# FPGA_Power_SPI.net
KiCad netlist of a schematic drawn in Altium Designer
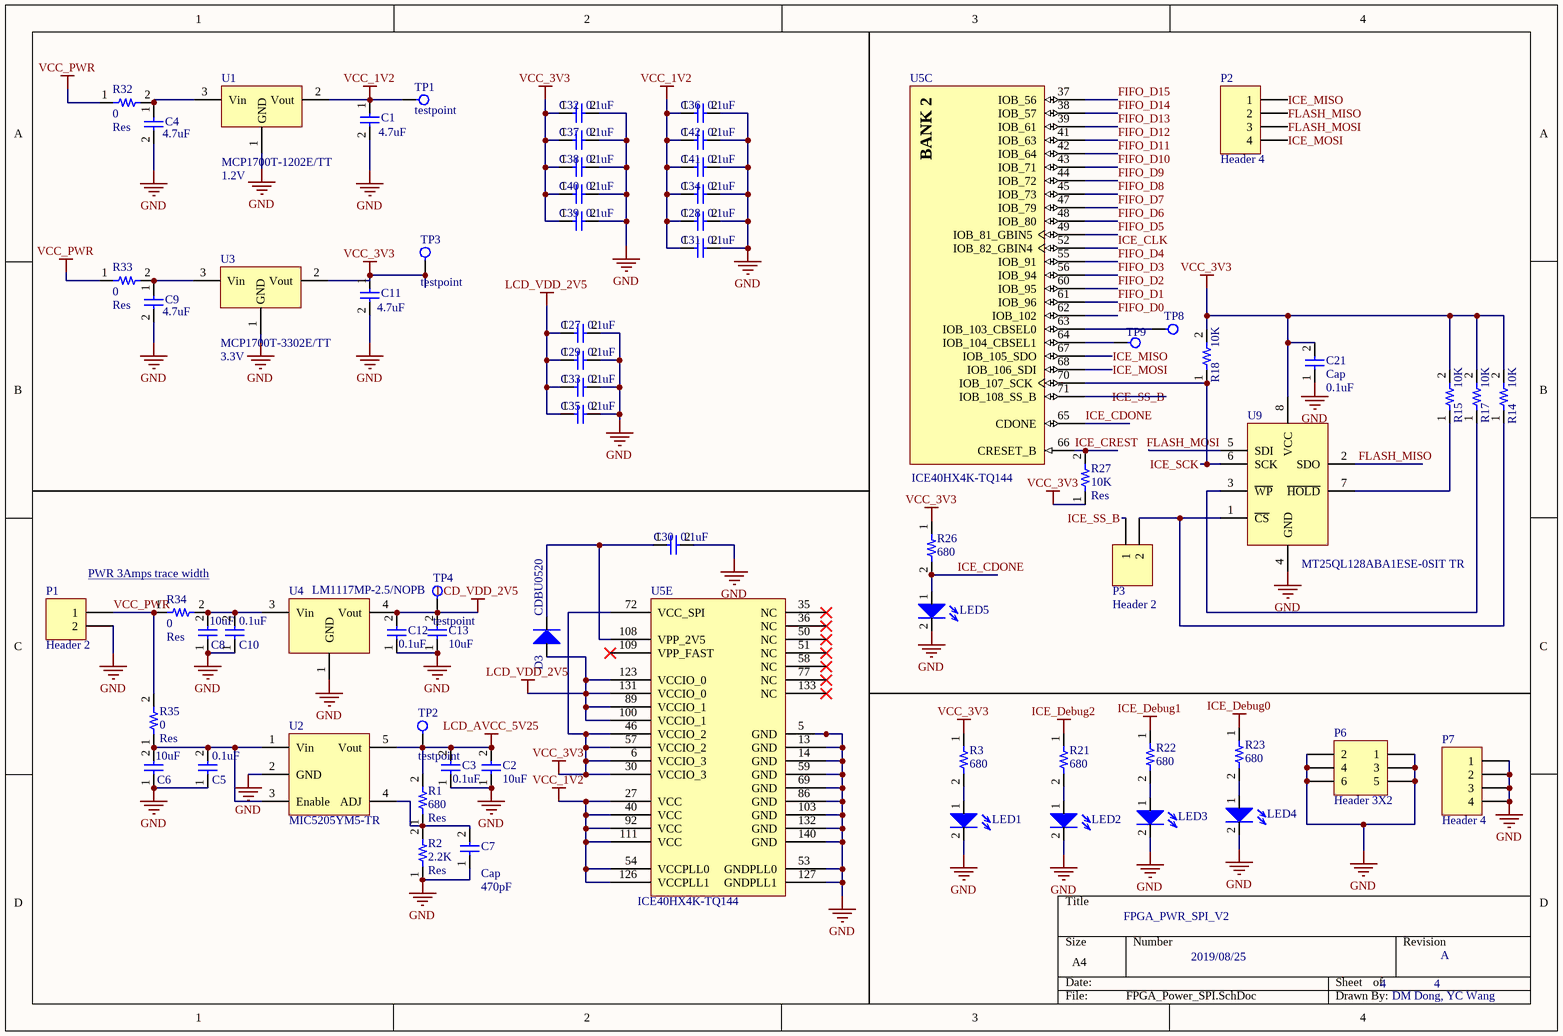
[diagram p0: FPGA_Power_SPI.SchDoc]

(export (version "E")
  (design (tool "Eeschema 10.0.6"))
  (components
    (comp (ref "C1")
      (value "4.7uF")
      (footprint "Cap_4.7uF")
      (description "Multilayer Ceramic Capacitors MLCC - SMD/SMT 6.3V 4.7uF 0603 X5R 10%")
      (fields (field (name "Comment") "C0603C475K9PAC7411") (field (name "CREATED BY") "Daoming Dong"))
      (libsource (lib "USB_FPGA_SLM_v1") (part "Cap_4.7uF"))
    )
    (comp (ref "C2")
      (value "10uF")
      (footprint "Cap_10uF")
      (description "Multilayer Ceramic Capacitors MLCC - SMD/SMT 0603 6.3V 10uF X5R 10% Soft Term")
      (fields (field (name "Comment") "C1608X5R0J106K080AE") (field (name "CREATED BY") "Daoming Dong"))
      (libsource (lib "USB_FPGA_SLM_v1") (part "Cap_10uF"))
    )
    (comp (ref "C3")
      (value "0.1uF")
      (footprint "Cap_0.1uF")
      (description "Multilayer Ceramic Capacitors MLCC - SMD/SMT 0.1uF 10% 50V AEC-Q200")
      (fields (field (name "Comment") "AC0603KRX7R9BB104") (field (name "CREATED BY") "Daoming Dong"))
      (libsource (lib "USB_FPGA_SLM_v1") (part "Cap_0.1uF"))
    )
    (comp (ref "C4")
      (value "4.7uF")
      (footprint "Cap_4.7uF")
      (description "Multilayer Ceramic Capacitors MLCC - SMD/SMT 6.3V 4.7uF 0603 X5R 10%")
      (fields (field (name "Comment") "C0603C475K9PAC7411") (field (name "CREATED BY") "Daoming Dong"))
      (libsource (lib "USB_FPGA_SLM_v1") (part "Cap_4.7uF"))
    )
    (comp (ref "C5")
      (value "0.1uF")
      (footprint "Cap_0.1uF")
      (description "Multilayer Ceramic Capacitors MLCC - SMD/SMT 0.1uF 10% 50V AEC-Q200")
      (fields (field (name "Comment") "AC0603KRX7R9BB104") (field (name "CREATED BY") "Daoming Dong"))
      (libsource (lib "USB_FPGA_SLM_v1") (part "Cap_0.1uF"))
    )
    (comp (ref "C6")
      (value "10uF")
      (footprint "Cap_10uF")
      (description "Multilayer Ceramic Capacitors MLCC - SMD/SMT 0603 6.3V 10uF X5R 10% Soft Term")
      (fields (field (name "Comment") "C1608X5R0J106K080AE") (field (name "CREATED BY") "Daoming Dong"))
      (libsource (lib "USB_FPGA_SLM_v1") (part "Cap_10uF"))
    )
    (comp (ref "C7")
      (value "470pF")
      (footprint "CAP_470pF")
      (description "Multilayer Ceramic Capacitors MLCC - SMD/SMT 25V 470pF X7R 0402 10% AEC-Q200")
      (fields
        (field (name "COMPONENT NAME") "Cap")
        (field (name "Comment") "C0402S471K3RACAUTO")
        (field (name "CREATED BY") "Daoming Dong")
      )
      (libsource (lib "USB_FPGA_SLM_v1") (part "Cap_470pF"))
    )
    (comp (ref "C8")
      (value "10uF")
      (footprint "Cap_10uF")
      (description "Multilayer Ceramic Capacitors MLCC - SMD/SMT 0603 6.3V 10uF X5R 10% Soft Term")
      (fields (field (name "Comment") "C1608X5R0J106K080AE") (field (name "CREATED BY") "Daoming Dong"))
      (libsource (lib "USB_FPGA_SLM_v1") (part "Cap_10uF"))
    )
    (comp (ref "C9")
      (value "4.7uF")
      (footprint "Cap_4.7uF")
      (description "Multilayer Ceramic Capacitors MLCC - SMD/SMT 6.3V 4.7uF 0603 X5R 10%")
      (fields (field (name "Comment") "C0603C475K9PAC7411") (field (name "CREATED BY") "Daoming Dong"))
      (libsource (lib "USB_FPGA_SLM_v1") (part "Cap_4.7uF"))
    )
    (comp (ref "C10")
      (value "0.1uF")
      (footprint "Cap_0.1uF")
      (description "Multilayer Ceramic Capacitors MLCC - SMD/SMT 0.1uF 10% 50V AEC-Q200")
      (fields (field (name "Comment") "AC0603KRX7R9BB104") (field (name "CREATED BY") "Daoming Dong"))
      (libsource (lib "USB_FPGA_SLM_v1") (part "Cap_0.1uF"))
    )
    (comp (ref "C11")
      (value "4.7uF")
      (footprint "Cap_4.7uF")
      (description "Multilayer Ceramic Capacitors MLCC - SMD/SMT 6.3V 4.7uF 0603 X5R 10%")
      (fields (field (name "Comment") "C0603C475K9PAC7411") (field (name "CREATED BY") "Daoming Dong"))
      (libsource (lib "USB_FPGA_SLM_v1") (part "Cap_4.7uF"))
    )
    (comp (ref "C12")
      (value "0.1uF")
      (footprint "Cap_0.1uF")
      (description "Multilayer Ceramic Capacitors MLCC - SMD/SMT 0.1uF 10% 50V AEC-Q200")
      (fields (field (name "Comment") "AC0603KRX7R9BB104") (field (name "CREATED BY") "Daoming Dong"))
      (libsource (lib "USB_FPGA_SLM_v1") (part "Cap_0.1uF"))
    )
    (comp (ref "C13")
      (value "10uF")
      (footprint "Cap_10uF")
      (description "Multilayer Ceramic Capacitors MLCC - SMD/SMT 0603 6.3V 10uF X5R 10% Soft Term")
      (fields (field (name "Comment") "C1608X5R0J106K080AE") (field (name "CREATED BY") "Daoming Dong"))
      (libsource (lib "USB_FPGA_SLM_v1") (part "Cap_10uF"))
    )
    (comp (ref "C21")
      (value "0.1uF")
      (footprint "Cap_0.1uF")
      (description "Multilayer Ceramic Capacitors MLCC - SMD/SMT 0.1uF 10% 50V AEC-Q200")
      (fields
        (field (name "COMPONENT NAME") "Cap")
        (field (name "Comment") "AC0603KRX7R9BB104")
        (field (name "CREATED BY") "Daoming Dong")
      )
      (libsource (lib "USB_FPGA_SLM_v1") (part "Cap_0.1uF"))
    )
    (comp (ref "C27")
      (value "0.1uF")
      (footprint "Cap_0.1uF")
      (description "Multilayer Ceramic Capacitors MLCC - SMD/SMT 0.1uF 10% 50V AEC-Q200")
      (fields (field (name "Comment") "AC0603KRX7R9BB104") (field (name "CREATED BY") "Daoming Dong"))
      (libsource (lib "USB_FPGA_SLM_v1") (part "Cap_0.1uF"))
    )
    (comp (ref "C28")
      (value "0.1uF")
      (footprint "Cap_0.1uF")
      (description "Multilayer Ceramic Capacitors MLCC - SMD/SMT 0.1uF 10% 50V AEC-Q200")
      (fields (field (name "Comment") "AC0603KRX7R9BB104") (field (name "CREATED BY") "Daoming Dong"))
      (libsource (lib "USB_FPGA_SLM_v1") (part "Cap_0.1uF"))
    )
    (comp (ref "C29")
      (value "0.1uF")
      (footprint "Cap_0.1uF")
      (description "Multilayer Ceramic Capacitors MLCC - SMD/SMT 0.1uF 10% 50V AEC-Q200")
      (fields (field (name "Comment") "AC0603KRX7R9BB104") (field (name "CREATED BY") "Daoming Dong"))
      (libsource (lib "USB_FPGA_SLM_v1") (part "Cap_0.1uF"))
    )
    (comp (ref "C30")
      (value "0.1uF")
      (footprint "Cap_0.1uF")
      (description "Multilayer Ceramic Capacitors MLCC - SMD/SMT 0.1uF 10% 50V AEC-Q200")
      (fields (field (name "Comment") "AC0603KRX7R9BB104") (field (name "CREATED BY") "Daoming Dong"))
      (libsource (lib "USB_FPGA_SLM_v1") (part "Cap_0.1uF"))
    )
    (comp (ref "C31")
      (value "0.1uF")
      (footprint "Cap_0.1uF")
      (description "Multilayer Ceramic Capacitors MLCC - SMD/SMT 0.1uF 10% 50V AEC-Q200")
      (fields (field (name "Comment") "AC0603KRX7R9BB104") (field (name "CREATED BY") "Daoming Dong"))
      (libsource (lib "USB_FPGA_SLM_v1") (part "Cap_0.1uF"))
    )
    (comp (ref "C32")
      (value "0.1uF")
      (footprint "Cap_0.1uF")
      (description "Multilayer Ceramic Capacitors MLCC - SMD/SMT 0.1uF 10% 50V AEC-Q200")
      (fields (field (name "Comment") "AC0603KRX7R9BB104") (field (name "CREATED BY") "Daoming Dong"))
      (libsource (lib "USB_FPGA_SLM_v1") (part "Cap_0.1uF"))
    )
    (comp (ref "C33")
      (value "0.1uF")
      (footprint "Cap_0.1uF")
      (description "Multilayer Ceramic Capacitors MLCC - SMD/SMT 0.1uF 10% 50V AEC-Q200")
      (fields (field (name "Comment") "AC0603KRX7R9BB104") (field (name "CREATED BY") "Daoming Dong"))
      (libsource (lib "USB_FPGA_SLM_v1") (part "Cap_0.1uF"))
    )
    (comp (ref "C34")
      (value "0.1uF")
      (footprint "Cap_0.1uF")
      (description "Multilayer Ceramic Capacitors MLCC - SMD/SMT 0.1uF 10% 50V AEC-Q200")
      (fields (field (name "Comment") "AC0603KRX7R9BB104") (field (name "CREATED BY") "Daoming Dong"))
      (libsource (lib "USB_FPGA_SLM_v1") (part "Cap_0.1uF"))
    )
    (comp (ref "C35")
      (value "0.1uF")
      (footprint "Cap_0.1uF")
      (description "Multilayer Ceramic Capacitors MLCC - SMD/SMT 0.1uF 10% 50V AEC-Q200")
      (fields (field (name "Comment") "AC0603KRX7R9BB104") (field (name "CREATED BY") "Daoming Dong"))
      (libsource (lib "USB_FPGA_SLM_v1") (part "Cap_0.1uF"))
    )
    (comp (ref "C36")
      (value "0.1uF")
      (footprint "Cap_0.1uF")
      (description "Multilayer Ceramic Capacitors MLCC - SMD/SMT 0.1uF 10% 50V AEC-Q200")
      (fields (field (name "Comment") "AC0603KRX7R9BB104") (field (name "CREATED BY") "Daoming Dong"))
      (libsource (lib "USB_FPGA_SLM_v1") (part "Cap_0.1uF"))
    )
    (comp (ref "C37")
      (value "0.1uF")
      (footprint "Cap_0.1uF")
      (description "Multilayer Ceramic Capacitors MLCC - SMD/SMT 0.1uF 10% 50V AEC-Q200")
      (fields (field (name "Comment") "AC0603KRX7R9BB104") (field (name "CREATED BY") "Daoming Dong"))
      (libsource (lib "USB_FPGA_SLM_v1") (part "Cap_0.1uF"))
    )
    (comp (ref "C38")
      (value "0.1uF")
      (footprint "Cap_0.1uF")
      (description "Multilayer Ceramic Capacitors MLCC - SMD/SMT 0.1uF 10% 50V AEC-Q200")
      (fields (field (name "Comment") "AC0603KRX7R9BB104") (field (name "CREATED BY") "Daoming Dong"))
      (libsource (lib "USB_FPGA_SLM_v1") (part "Cap_0.1uF"))
    )
    (comp (ref "C39")
      (value "0.1uF")
      (footprint "Cap_0.1uF")
      (description "Multilayer Ceramic Capacitors MLCC - SMD/SMT 0.1uF 10% 50V AEC-Q200")
      (fields (field (name "Comment") "AC0603KRX7R9BB104") (field (name "CREATED BY") "Daoming Dong"))
      (libsource (lib "USB_FPGA_SLM_v1") (part "Cap_0.1uF"))
    )
    (comp (ref "C40")
      (value "0.1uF")
      (footprint "Cap_0.1uF")
      (description "Multilayer Ceramic Capacitors MLCC - SMD/SMT 0.1uF 10% 50V AEC-Q200")
      (fields (field (name "Comment") "AC0603KRX7R9BB104") (field (name "CREATED BY") "Daoming Dong"))
      (libsource (lib "USB_FPGA_SLM_v1") (part "Cap_0.1uF"))
    )
    (comp (ref "C41")
      (value "0.1uF")
      (footprint "Cap_0.1uF")
      (description "Multilayer Ceramic Capacitors MLCC - SMD/SMT 0.1uF 10% 50V AEC-Q200")
      (fields (field (name "Comment") "AC0603KRX7R9BB104") (field (name "CREATED BY") "Daoming Dong"))
      (libsource (lib "USB_FPGA_SLM_v1") (part "Cap_0.1uF"))
    )
    (comp (ref "C42")
      (value "0.1uF")
      (footprint "Cap_0.1uF")
      (description "Multilayer Ceramic Capacitors MLCC - SMD/SMT 0.1uF 10% 50V AEC-Q200")
      (fields (field (name "Comment") "AC0603KRX7R9BB104") (field (name "CREATED BY") "Daoming Dong"))
      (libsource (lib "USB_FPGA_SLM_v1") (part "Cap_0.1uF"))
    )
    (comp (ref "D3")
      (value "CDBU0520")
      (footprint "SchottkyDiode_CDBU0520")
      (description "Schottky Diodes & Rectifiers VR=20V, IO=500mA")
      (fields (field (name "CREATED BY") "Daoming Dong"))
      (libsource (lib "USB_FPGA_SLM_v1") (part "SDiode_CDBU0520"))
    )
    (comp (ref "LED1")
      (value "TLMS1000-GS08")
      (footprint "LED_RED")
      (description "Standard LEDs - SMD RED")
      (fields (field (name "CREATED BY") "Daoming Dong"))
      (libsource (lib "USB_FPGA_SLM_v1") (part "LED_RED"))
    )
    (comp (ref "LED2")
      (value "TLMS1000-GS08")
      (footprint "LED_RED")
      (description "Standard LEDs - SMD RED")
      (fields (field (name "CREATED BY") "Daoming Dong"))
      (libsource (lib "USB_FPGA_SLM_v1") (part "LED_RED"))
    )
    (comp (ref "LED3")
      (value "TLMS1000-GS08")
      (footprint "LED_RED")
      (description "Standard LEDs - SMD RED")
      (fields (field (name "CREATED BY") "Daoming Dong"))
      (libsource (lib "USB_FPGA_SLM_v1") (part "LED_RED"))
    )
    (comp (ref "LED4")
      (value "TLMS1000-GS08")
      (footprint "LED_RED")
      (description "Standard LEDs - SMD RED")
      (fields (field (name "CREATED BY") "Daoming Dong"))
      (libsource (lib "USB_FPGA_SLM_v1") (part "LED_RED"))
    )
    (comp (ref "LED5")
      (value "TLMS1000-GS08")
      (footprint "LED_RED")
      (description "Standard LEDs - SMD RED")
      (fields (field (name "CREATED BY") "Daoming Dong"))
      (libsource (lib "USB_FPGA_SLM_v1") (part "LED_RED"))
    )
    (comp (ref "P1")
      (value "Header 2")
      (footprint "HDR1X2")
      (description "Header, 2-Pin")
      (fields (field (name "PUBLISHER") "Altium Limited"))
      (libsource (lib "") (part "Header 2_1"))
    )
    (comp (ref "P2")
      (value "Header 4")
      (footprint "HDR2X2")
      (description "Header, 4-Pin")
      (fields (field (name "PUBLISHER") "Altium Limited"))
      (libsource (lib "Miscellaneous Connectors") (part "Header 4"))
    )
    (comp (ref "P3")
      (value "Header 2")
      (footprint "HDR1X2")
      (description "Header, 2-Pin")
      (fields (field (name "PUBLISHER") "Altium Limited"))
      (libsource (lib "Miscellaneous Connectors") (part "Header 2"))
    )
    (comp (ref "P6")
      (value "Header 3X2")
      (footprint "HDR2X3")
      (description "Header, 3-Pin, Dual row")
      (fields (field (name "PUBLISHER") "Altium Limited"))
      (libsource (lib "Miscellaneous Connectors") (part "Header 3X2"))
    )
    (comp (ref "P7")
      (value "Header 4")
      (footprint "HDR2X2")
      (description "Header, 4-Pin")
      (fields (field (name "PUBLISHER") "Altium Limited"))
      (libsource (lib "Miscellaneous Connectors") (part "Header 4"))
    )
    (comp (ref "R1")
      (value "680")
      (footprint "RES_680")
      (description "Thin Film Resistors - SMD 680 ohm 1% 50 ppm Thin Film")
      (fields
        (field (name "COMPONENT NAME") "Res")
        (field (name "Comment") "RT0603FRE13680RL")
        (field (name "CREATED BY") "Daoming Dong")
      )
      (libsource (lib "USB_FPGA_SLM_v1") (part "Res_680"))
    )
    (comp (ref "R2")
      (value "2.2K")
      (footprint "RES_2.2K")
      (description "Thick Film Resistors - SMD 1/10Watt 2.2Kohms 5% Commercial Use")
      (fields
        (field (name "COMPONENT NAME") "Res")
        (field (name "Comment") "CRCW06032K20JNEAC")
        (field (name "CREATED BY") "Daoming Dong")
      )
      (libsource (lib "USB_FPGA_SLM_v1") (part "Res_2.2K"))
    )
    (comp (ref "R3")
      (value "680")
      (footprint "RES_680")
      (description "Thin Film Resistors - SMD 680 ohm 1% 50 ppm Thin Film")
      (fields (field (name "Comment") "RT0603FRE13680RL") (field (name "CREATED BY") "Daoming Dong"))
      (libsource (lib "USB_FPGA_SLM_v1") (part "Res_680"))
    )
    (comp (ref "R14")
      (value "10K")
      (footprint "RES_10K")
      (description "Thin Film Resistors - SMD 10K ohm 0.05% 50 ppm High-Precision")
      (fields (field (name "Comment") "RT0603WRE0710KL") (field (name "CREATED BY") "Daoming Dong"))
      (libsource (lib "USB_FPGA_SLM_v1") (part "Res_10K"))
    )
    (comp (ref "R15")
      (value "10K")
      (footprint "RES_10K")
      (description "Thin Film Resistors - SMD 10K ohm 0.05% 50 ppm High-Precision")
      (fields (field (name "Comment") "RT0603WRE0710KL") (field (name "CREATED BY") "Daoming Dong"))
      (libsource (lib "USB_FPGA_SLM_v1") (part "Res_10K"))
    )
    (comp (ref "R17")
      (value "10K")
      (footprint "RES_10K")
      (description "Thin Film Resistors - SMD 10K ohm 0.05% 50 ppm High-Precision")
      (fields (field (name "Comment") "RT0603WRE0710KL") (field (name "CREATED BY") "Daoming Dong"))
      (libsource (lib "USB_FPGA_SLM_v1") (part "Res_10K"))
    )
    (comp (ref "R18")
      (value "10K")
      (footprint "RES_10K")
      (description "Thin Film Resistors - SMD 10K ohm 0.05% 50 ppm High-Precision")
      (fields (field (name "Comment") "RT0603WRE0710KL") (field (name "CREATED BY") "Daoming Dong"))
      (libsource (lib "USB_FPGA_SLM_v1") (part "Res_10K"))
    )
    (comp (ref "R21")
      (value "680")
      (footprint "RES_680")
      (description "Thin Film Resistors - SMD 680 ohm 1% 50 ppm Thin Film")
      (fields (field (name "Comment") "RT0603FRE13680RL") (field (name "CREATED BY") "Daoming Dong"))
      (libsource (lib "USB_FPGA_SLM_v1") (part "Res_680"))
    )
    (comp (ref "R22")
      (value "680")
      (footprint "RES_680")
      (description "Thin Film Resistors - SMD 680 ohm 1% 50 ppm Thin Film")
      (fields (field (name "Comment") "RT0603FRE13680RL") (field (name "CREATED BY") "Daoming Dong"))
      (libsource (lib "USB_FPGA_SLM_v1") (part "Res_680"))
    )
    (comp (ref "R23")
      (value "680")
      (footprint "RES_680")
      (description "Thin Film Resistors - SMD 680 ohm 1% 50 ppm Thin Film")
      (fields (field (name "Comment") "RT0603FRE13680RL") (field (name "CREATED BY") "Daoming Dong"))
      (libsource (lib "USB_FPGA_SLM_v1") (part "Res_680"))
    )
    (comp (ref "R26")
      (value "680")
      (footprint "RES_680")
      (description "Thin Film Resistors - SMD 680 ohm 1% 50 ppm Thin Film")
      (fields (field (name "Comment") "RT0603FRE13680RL") (field (name "CREATED BY") "Daoming Dong"))
      (libsource (lib "USB_FPGA_SLM_v1") (part "Res_680"))
    )
    (comp (ref "R27")
      (value "10K")
      (footprint "RES_10K")
      (description "Thin Film Resistors - SMD 10K ohm 0.05% 50 ppm High-Precision")
      (fields
        (field (name "COMPONENT NAME") "Res")
        (field (name "Comment") "RT0603WRE0710KL")
        (field (name "CREATED BY") "Daoming Dong")
      )
      (libsource (lib "USB_FPGA_SLM_v1") (part "Res_10K"))
    )
    (comp (ref "R32")
      (value "0")
      (footprint "RES_0")
      (description "Thick Film Resistors - SMD 1/10Watt 0ohms Commercial Use")
      (fields
        (field (name "COMPONENT NAME") "Res")
        (field (name "Comment") "CRCW06030000Z0EAC")
        (field (name "CREATED BY") "Daoming Dong")
      )
      (libsource (lib "USB_FPGA_SLM_v1") (part "Res_0"))
    )
    (comp (ref "R33")
      (value "0")
      (footprint "RES_0")
      (description "Thick Film Resistors - SMD 1/10Watt 0ohms Commercial Use")
      (fields
        (field (name "COMPONENT NAME") "Res")
        (field (name "Comment") "CRCW06030000Z0EAC")
        (field (name "CREATED BY") "Daoming Dong")
      )
      (libsource (lib "USB_FPGA_SLM_v1") (part "Res_0"))
    )
    (comp (ref "R34")
      (value "0")
      (footprint "RES_0")
      (description "Thick Film Resistors - SMD 1/10Watt 0ohms Commercial Use")
      (fields
        (field (name "COMPONENT NAME") "Res")
        (field (name "Comment") "CRCW06030000Z0EAC")
        (field (name "CREATED BY") "Daoming Dong")
      )
      (libsource (lib "USB_FPGA_SLM_v1") (part "Res_0"))
    )
    (comp (ref "R35")
      (value "0")
      (footprint "RES_0")
      (description "Thick Film Resistors - SMD 1/10Watt 0ohms Commercial Use")
      (fields
        (field (name "COMPONENT NAME") "Res")
        (field (name "Comment") "CRCW06030000Z0EAC")
        (field (name "CREATED BY") "Daoming Dong")
      )
      (libsource (lib "USB_FPGA_SLM_v1") (part "Res_0"))
    )
    (comp (ref "TP1")
      (value "testpoint")
      (footprint "testpoint")
      (description "Testpoint for testing voltage")
      (fields (field (name "CREATED BY") "Daoming Dong"))
      (libsource (lib "USB_FPGA_SLM_v1") (part "Testpoint"))
    )
    (comp (ref "TP2")
      (value "testpoint")
      (footprint "testpoint")
      (description "Testpoint for testing voltage")
      (fields (field (name "CREATED BY") "Daoming Dong"))
      (libsource (lib "USB_FPGA_SLM_v1") (part "Testpoint"))
    )
    (comp (ref "TP3")
      (value "testpoint")
      (footprint "testpoint")
      (description "Testpoint for testing voltage")
      (fields (field (name "CREATED BY") "Daoming Dong"))
      (libsource (lib "USB_FPGA_SLM_v1") (part "Testpoint"))
    )
    (comp (ref "TP4")
      (value "testpoint")
      (footprint "testpoint")
      (description "Testpoint for testing voltage")
      (fields (field (name "CREATED BY") "Daoming Dong"))
      (libsource (lib "USB_FPGA_SLM_v1") (part "Testpoint"))
    )
    (comp (ref "TP8")
      (value "Testpoint")
      (footprint "testpoint")
      (description "Testpoint for testing voltage")
      (fields (field (name "CREATED BY") "Daoming Dong"))
      (libsource (lib "USB_FPGA_SLM_v1") (part "Testpoint"))
    )
    (comp (ref "TP9")
      (value "Testpoint")
      (footprint "testpoint")
      (description "Testpoint for testing voltage")
      (fields (field (name "CREATED BY") "Daoming Dong"))
      (libsource (lib "USB_FPGA_SLM_v1") (part "Testpoint"))
    )
    (comp (ref "U1")
      (value "MCP1700T-1202E/TT")
      (footprint "MIC_LDO_1V2")
      (description "LDO Voltage Regulators 250mA Adj LDO 2%")
      (fields (field (name "ALTIUM_VALUE") "1.2V") (field (name "CREATED BY") "Daoming Dong"))
      (libsource (lib "USB_FPGA_SLM_v1") (part "MIC_LDO_1V2"))
    )
    (comp (ref "U2")
      (value "MIC5205YM5-TR")
      (footprint "MIC5205YM5")
      (description "LDO Voltage Regulators 150mA 1% Low Noise LDO")
      (fields (field (name "CREATED BY") "Daoming Dong"))
      (libsource (lib "USB_FPGA_SLM_v1") (part "MIC5205YM5"))
    )
    (comp (ref "U3")
      (value "MCP1700T-3302E/TT")
      (footprint "MIC_LDO_3V3")
      (description "3.3v LDO Voltage Regulators 250mA Adj LDO 2%")
      (fields (field (name "ALTIUM_VALUE") "3.3V") (field (name "CREATED BY") "Daoming Dong"))
      (libsource (lib "USB_FPGA_SLM_v1") (part "MIC_LDO_3V3"))
    )
    (comp (ref "U4")
      (value "LM1117MP-2.5/NOPB")
      (footprint "LM1117MP-2.5/NOPB")
      (description "LDO Voltage Regulators 800mA LDO Linear Reg")
      (fields (field (name "CREATED BY") "Daoming Dong"))
      (libsource (lib "USB_FPGA_SLM_v1") (part "LDO_2V5"))
    )
    (comp (ref "U5")
      (value "ICE40HX4K-TQ144")
      (footprint "LATC-TQFP-144_L")
      (fields (field (name "MANUFACTURER") "Lattice Semiconductor"))
      (libsource (lib "Lattice iCE40") (part "ICE40HX4K-TQ144"))
    )
    (comp (ref "U9")
      (value "MT25QL128ABA1ESE-0SIT TR")
      (footprint "Flash")
      (description "NOR Flash SPI FLASH NOR SLC 32MX4 SOIC")
      (fields (field (name "CREATED BY") "Daoming Dong"))
      (libsource (lib "USB_FPGA_SLM_v1") (part "Flash"))
    )
  )
  (nets
    (net (code "1") (name "/FIFO_D0") (class "Default")
      (node (ref "U5") (pin "62") (pinfunction "IOB_102_62") (pintype "bidirectional"))
    )
    (net (code "2") (name "/FIFO_D1") (class "Default")
      (node (ref "U5") (pin "61") (pinfunction "IOB_96_61") (pintype "bidirectional"))
    )
    (net (code "3") (name "/FIFO_D2") (class "Default")
      (node (ref "U5") (pin "60") (pinfunction "IOB_95_60") (pintype "bidirectional"))
    )
    (net (code "4") (name "/FIFO_D3") (class "Default")
      (node (ref "U5") (pin "56") (pinfunction "IOB_94_56") (pintype "bidirectional"))
    )
    (net (code "5") (name "/FIFO_D4") (class "Default")
      (node (ref "U5") (pin "55") (pinfunction "IOB_91_55") (pintype "bidirectional"))
    )
    (net (code "6") (name "/FIFO_D5") (class "Default")
      (node (ref "U5") (pin "49") (pinfunction "IOB_81_GBIN5_49") (pintype "bidirectional"))
    )
    (net (code "7") (name "/FIFO_D6") (class "Default")
      (node (ref "U5") (pin "48") (pinfunction "IOB_80_48") (pintype "bidirectional"))
    )
    (net (code "8") (name "/FIFO_D7") (class "Default")
      (node (ref "U5") (pin "47") (pinfunction "IOB_79_47") (pintype "bidirectional"))
    )
    (net (code "9") (name "/FIFO_D8") (class "Default")
      (node (ref "U5") (pin "45") (pinfunction "IOB_73_45") (pintype "bidirectional"))
    )
    (net (code "10") (name "/FIFO_D9") (class "Default")
      (node (ref "U5") (pin "44") (pinfunction "IOB_72_44") (pintype "bidirectional"))
    )
    (net (code "11") (name "/FIFO_D10") (class "Default")
      (node (ref "U5") (pin "43") (pinfunction "IOB_71_43") (pintype "bidirectional"))
    )
    (net (code "12") (name "/FIFO_D11") (class "Default")
      (node (ref "U5") (pin "42") (pinfunction "IOB_64_42") (pintype "bidirectional"))
    )
    (net (code "13") (name "/FIFO_D12") (class "Default")
      (node (ref "U5") (pin "41") (pinfunction "IOB_63_41") (pintype "bidirectional"))
    )
    (net (code "14") (name "/FIFO_D13") (class "Default")
      (node (ref "U5") (pin "39") (pinfunction "IOB_61_39") (pintype "bidirectional"))
    )
    (net (code "15") (name "/FIFO_D14") (class "Default")
      (node (ref "U5") (pin "38") (pinfunction "IOB_57_38") (pintype "bidirectional"))
    )
    (net (code "16") (name "/FIFO_D15") (class "Default")
      (node (ref "U5") (pin "37") (pinfunction "IOB_56_37") (pintype "bidirectional"))
    )
    (net (code "17") (name "/FLASH_MISO") (class "Default")
      (node (ref "P2") (pin "2") (pinfunction "2_2") (pintype "passive"))
      (node (ref "U9") (pin "2") (pinfunction "SDO_2") (pintype "passive"))
    )
    (net (code "18") (name "/FLASH_MOSI") (class "Default")
      (node (ref "P2") (pin "3") (pinfunction "3_3") (pintype "passive"))
      (node (ref "U9") (pin "5") (pinfunction "SDI_5") (pintype "passive"))
    )
    (net (code "19") (name "/ICE_CDONE") (class "Default")
      (node (ref "LED5") (pin "1") (pinfunction "Anode_1") (pintype "passive"))
      (node (ref "R26") (pin "2") (pinfunction "2_2") (pintype "passive"))
      (node (ref "U5") (pin "65") (pinfunction "CDONE_65") (pintype "bidirectional"))
    )
    (net (code "20") (name "/ICE_CLK") (class "Default")
      (node (ref "U5") (pin "52") (pinfunction "IOB_82_GBIN4_52") (pintype "bidirectional"))
    )
    (net (code "21") (name "/ICE_CREST") (class "Default")
      (node (ref "R27") (pin "2") (pinfunction "2_2") (pintype "passive"))
      (node (ref "U5") (pin "66") (pinfunction "CRESET_B_66") (pintype "input"))
    )
    (net (code "22") (name "/ICE_MISO") (class "Default")
      (node (ref "P2") (pin "1") (pinfunction "1_1") (pintype "passive"))
      (node (ref "U5") (pin "67") (pinfunction "IOB_105_SDO_67") (pintype "bidirectional"))
    )
    (net (code "23") (name "/ICE_MOSI") (class "Default")
      (node (ref "P2") (pin "4") (pinfunction "4_4") (pintype "passive"))
      (node (ref "U5") (pin "68") (pinfunction "IOB_106_SDI_68") (pintype "bidirectional"))
    )
    (net (code "24") (name "/ICE_SCK") (class "Default")
      (node (ref "R18") (pin "1") (pinfunction "1_1") (pintype "passive"))
      (node (ref "U5") (pin "70") (pinfunction "IOB_107_SCK_70") (pintype "bidirectional"))
      (node (ref "U9") (pin "6") (pinfunction "SCK_6") (pintype "passive"))
    )
    (net (code "25") (name "/ICE_SS_B") (class "Default")
      (node (ref "P3") (pin "1") (pinfunction "1_1") (pintype "passive"))
      (node (ref "U5") (pin "71") (pinfunction "IOB_108_SS_B_71") (pintype "bidirectional"))
    )
    (net (code "26") (name "GND") (class "Default")
      (node (ref "C1") (pin "2") (pinfunction "2_2") (pintype "passive"))
      (node (ref "C10") (pin "1") (pinfunction "1_1") (pintype "passive"))
      (node (ref "C11") (pin "2") (pinfunction "2_2") (pintype "passive"))
      (node (ref "C12") (pin "1") (pinfunction "1_1") (pintype "passive"))
      (node (ref "C13") (pin "1") (pinfunction "1_1") (pintype "passive"))
      (node (ref "C2") (pin "1") (pinfunction "1_1") (pintype "passive"))
      (node (ref "C21") (pin "1") (pinfunction "1_1") (pintype "passive"))
      (node (ref "C27") (pin "2") (pinfunction "2_2") (pintype "passive"))
      (node (ref "C28") (pin "2") (pinfunction "2_2") (pintype "passive"))
      (node (ref "C29") (pin "2") (pinfunction "2_2") (pintype "passive"))
      (node (ref "C3") (pin "1") (pinfunction "1_1") (pintype "passive"))
      (node (ref "C30") (pin "2") (pinfunction "2_2") (pintype "passive"))
      (node (ref "C31") (pin "2") (pinfunction "2_2") (pintype "passive"))
      (node (ref "C32") (pin "2") (pinfunction "2_2") (pintype "passive"))
      (node (ref "C33") (pin "2") (pinfunction "2_2") (pintype "passive"))
      (node (ref "C34") (pin "2") (pinfunction "2_2") (pintype "passive"))
      (node (ref "C35") (pin "2") (pinfunction "2_2") (pintype "passive"))
      (node (ref "C36") (pin "2") (pinfunction "2_2") (pintype "passive"))
      (node (ref "C37") (pin "2") (pinfunction "2_2") (pintype "passive"))
      (node (ref "C38") (pin "2") (pinfunction "2_2") (pintype "passive"))
      (node (ref "C39") (pin "2") (pinfunction "2_2") (pintype "passive"))
      (node (ref "C4") (pin "2") (pinfunction "2_2") (pintype "passive"))
      (node (ref "C40") (pin "2") (pinfunction "2_2") (pintype "passive"))
      (node (ref "C41") (pin "2") (pinfunction "2_2") (pintype "passive"))
      (node (ref "C42") (pin "2") (pinfunction "2_2") (pintype "passive"))
      (node (ref "C5") (pin "1") (pinfunction "1_1") (pintype "passive"))
      (node (ref "C6") (pin "1") (pinfunction "1_1") (pintype "passive"))
      (node (ref "C7") (pin "1") (pinfunction "1_1") (pintype "passive"))
      (node (ref "C8") (pin "1") (pinfunction "1_1") (pintype "passive"))
      (node (ref "C9") (pin "2") (pinfunction "2_2") (pintype "passive"))
      (node (ref "LED1") (pin "2") (pinfunction "Cathode_2") (pintype "passive"))
      (node (ref "LED2") (pin "2") (pinfunction "Cathode_2") (pintype "passive"))
      (node (ref "LED3") (pin "2") (pinfunction "Cathode_2") (pintype "passive"))
      (node (ref "LED4") (pin "2") (pinfunction "Cathode_2") (pintype "passive"))
      (node (ref "LED5") (pin "2") (pinfunction "Cathode_2") (pintype "passive"))
      (node (ref "P1") (pin "2") (pinfunction "2_2") (pintype "passive"))
      (node (ref "P6") (pin "1") (pinfunction "1_1") (pintype "passive"))
      (node (ref "P6") (pin "2") (pinfunction "2_2") (pintype "passive"))
      (node (ref "P6") (pin "3") (pinfunction "3_3") (pintype "passive"))
      (node (ref "P6") (pin "4") (pinfunction "4_4") (pintype "passive"))
      (node (ref "P6") (pin "5") (pinfunction "5_5") (pintype "passive"))
      (node (ref "P6") (pin "6") (pinfunction "6_6") (pintype "passive"))
      (node (ref "P7") (pin "1") (pinfunction "1_1") (pintype "passive"))
      (node (ref "P7") (pin "2") (pinfunction "2_2") (pintype "passive"))
      (node (ref "P7") (pin "3") (pinfunction "3_3") (pintype "passive"))
      (node (ref "P7") (pin "4") (pinfunction "4_4") (pintype "passive"))
      (node (ref "R2") (pin "1") (pinfunction "1_1") (pintype "passive"))
      (node (ref "U1") (pin "1") (pinfunction "GND_1") (pintype "passive"))
      (node (ref "U2") (pin "2") (pinfunction "GND_2") (pintype "passive"))
      (node (ref "U3") (pin "1") (pinfunction "GND_1") (pintype "passive"))
      (node (ref "U4") (pin "1") (pinfunction "GND_1") (pintype "passive"))
      (node (ref "U5") (pin "103") (pinfunction "GND_103") (pintype "power_in"))
      (node (ref "U5") (pin "127") (pinfunction "GNDPLL1_127") (pintype "power_in"))
      (node (ref "U5") (pin "13") (pinfunction "GND_13") (pintype "power_in"))
      (node (ref "U5") (pin "132") (pinfunction "GND_132") (pintype "power_in"))
      (node (ref "U5") (pin "14") (pinfunction "GND_14") (pintype "power_in"))
      (node (ref "U5") (pin "140") (pinfunction "GND_140") (pintype "power_in"))
      (node (ref "U5") (pin "5") (pinfunction "GND_5") (pintype "power_in"))
      (node (ref "U5") (pin "53") (pinfunction "GNDPLL0_53") (pintype "power_in"))
      (node (ref "U5") (pin "59") (pinfunction "GND_59") (pintype "power_in"))
      (node (ref "U5") (pin "69") (pinfunction "GND_69") (pintype "power_in"))
      (node (ref "U5") (pin "86") (pinfunction "GND_86") (pintype "power_in"))
      (node (ref "U9") (pin "4") (pinfunction "GND_4") (pintype "passive"))
    )
    (net (code "27") (name "ICE_Debug0") (class "Default")
      (node (ref "R23") (pin "1") (pinfunction "1_1") (pintype "passive"))
    )
    (net (code "28") (name "ICE_Debug1") (class "Default")
      (node (ref "R22") (pin "1") (pinfunction "1_1") (pintype "passive"))
    )
    (net (code "29") (name "ICE_Debug2") (class "Default")
      (node (ref "R21") (pin "1") (pinfunction "1_1") (pintype "passive"))
    )
    (net (code "30") (name "LCD_AVCC_5V25") (class "Default")
      (node (ref "C2") (pin "2") (pinfunction "2_2") (pintype "passive"))
      (node (ref "C3") (pin "2") (pinfunction "2_2") (pintype "passive"))
      (node (ref "R1") (pin "2") (pinfunction "2_2") (pintype "passive"))
      (node (ref "TP2") (pin "1") (pinfunction "1_1") (pintype "passive"))
      (node (ref "U2") (pin "5") (pinfunction "Vout_5") (pintype "passive"))
    )
    (net (code "31") (name "LCD_VDD_2V5") (class "Default")
      (node (ref "C12") (pin "2") (pinfunction "2_2") (pintype "passive"))
      (node (ref "C13") (pin "2") (pinfunction "2_2") (pintype "passive"))
      (node (ref "C27") (pin "1") (pinfunction "1_1") (pintype "passive"))
      (node (ref "C29") (pin "1") (pinfunction "1_1") (pintype "passive"))
      (node (ref "C33") (pin "1") (pinfunction "1_1") (pintype "passive"))
      (node (ref "C35") (pin "1") (pinfunction "1_1") (pintype "passive"))
      (node (ref "D3") (pin "1") (pinfunction "Anode_1") (pintype "passive"))
      (node (ref "TP4") (pin "1") (pinfunction "1_1") (pintype "passive"))
      (node (ref "U4") (pin "4") (pinfunction "Vout_4") (pintype "power_in"))
      (node (ref "U5") (pin "100") (pinfunction "VCCIO_1_100") (pintype "power_in"))
      (node (ref "U5") (pin "123") (pinfunction "VCCIO_0_123") (pintype "power_in"))
      (node (ref "U5") (pin "131") (pinfunction "VCCIO_0_131") (pintype "power_in"))
      (node (ref "U5") (pin "89") (pinfunction "VCCIO_1_89") (pintype "power_in"))
    )
    (net (code "32") (name "Net-(D3-Cathode)") (class "Default")
      (node (ref "C30") (pin "1") (pinfunction "1_1") (pintype "passive"))
      (node (ref "D3") (pin "2") (pinfunction "Cathode_2") (pintype "passive"))
      (node (ref "U5") (pin "108") (pinfunction "VPP_2V5_108") (pintype "power_in"))
    )
    (net (code "33") (name "Net-(LED1-Anode)") (class "Default")
      (node (ref "LED1") (pin "1") (pinfunction "Anode_1") (pintype "passive"))
      (node (ref "R3") (pin "2") (pinfunction "2_2") (pintype "passive"))
    )
    (net (code "34") (name "Net-(LED2-Anode)") (class "Default")
      (node (ref "LED2") (pin "1") (pinfunction "Anode_1") (pintype "passive"))
      (node (ref "R21") (pin "2") (pinfunction "2_2") (pintype "passive"))
    )
    (net (code "35") (name "Net-(LED3-Anode)") (class "Default")
      (node (ref "LED3") (pin "1") (pinfunction "Anode_1") (pintype "passive"))
      (node (ref "R22") (pin "2") (pinfunction "2_2") (pintype "passive"))
    )
    (net (code "36") (name "Net-(LED4-Anode)") (class "Default")
      (node (ref "LED4") (pin "1") (pinfunction "Anode_1") (pintype "passive"))
      (node (ref "R23") (pin "2") (pinfunction "2_2") (pintype "passive"))
    )
    (net (code "37") (name "Net-(U1-Vin)") (class "Default")
      (node (ref "C4") (pin "1") (pinfunction "1_1") (pintype "passive"))
      (node (ref "R32") (pin "2") (pinfunction "2_2") (pintype "passive"))
      (node (ref "U1") (pin "3") (pinfunction "Vin_3") (pintype "passive"))
    )
    (net (code "38") (name "Net-(U2-ADJ)") (class "Default")
      (node (ref "C7") (pin "2") (pinfunction "2_2") (pintype "passive"))
      (node (ref "R1") (pin "1") (pinfunction "1_1") (pintype "passive"))
      (node (ref "R2") (pin "2") (pinfunction "2_2") (pintype "passive"))
      (node (ref "U2") (pin "4") (pinfunction "ADJ_4") (pintype "passive"))
    )
    (net (code "39") (name "Net-(U2-Enable)") (class "Default")
      (node (ref "C5") (pin "2") (pinfunction "2_2") (pintype "passive"))
      (node (ref "C6") (pin "2") (pinfunction "2_2") (pintype "passive"))
      (node (ref "R35") (pin "1") (pinfunction "1_1") (pintype "passive"))
      (node (ref "U2") (pin "1") (pinfunction "Vin_1") (pintype "passive"))
      (node (ref "U2") (pin "3") (pinfunction "Enable_3") (pintype "passive"))
    )
    (net (code "40") (name "Net-(U3-Vin)") (class "Default")
      (node (ref "C9") (pin "1") (pinfunction "1_1") (pintype "passive"))
      (node (ref "R33") (pin "2") (pinfunction "2_2") (pintype "passive"))
      (node (ref "U3") (pin "3") (pinfunction "Vin_3") (pintype "passive"))
    )
    (net (code "41") (name "Net-(U4-Vin)") (class "Default")
      (node (ref "C10") (pin "2") (pinfunction "2_2") (pintype "passive"))
      (node (ref "C8") (pin "2") (pinfunction "2_2") (pintype "passive"))
      (node (ref "R34") (pin "2") (pinfunction "2_2") (pintype "passive"))
      (node (ref "U4") (pin "3") (pinfunction "Vin_3") (pintype "power_in"))
    )
    (net (code "42") (name "Net-(U5C-IOB_103_CBSEL0)") (class "Default")
      (node (ref "TP8") (pin "1") (pinfunction "1_1") (pintype "passive"))
      (node (ref "U5") (pin "63") (pinfunction "IOB_103_CBSEL0_63") (pintype "bidirectional"))
    )
    (net (code "43") (name "Net-(U5C-IOB_104_CBSEL1)") (class "Default")
      (node (ref "TP9") (pin "1") (pinfunction "1_1") (pintype "passive"))
      (node (ref "U5") (pin "64") (pinfunction "IOB_104_CBSEL1_64") (pintype "bidirectional"))
    )
    (net (code "44") (name "Net-(U9-~{CS})") (class "Default")
      (node (ref "P3") (pin "2") (pinfunction "2_2") (pintype "passive"))
      (node (ref "R14") (pin "1") (pinfunction "1_1") (pintype "passive"))
      (node (ref "U9") (pin "1") (pinfunction "~{CS}_1") (pintype "passive"))
    )
    (net (code "45") (name "Net-(U9-~{HOLD})") (class "Default")
      (node (ref "R15") (pin "1") (pinfunction "1_1") (pintype "passive"))
      (node (ref "U9") (pin "7") (pinfunction "~{HOLD}_7") (pintype "passive"))
    )
    (net (code "46") (name "Net-(U9-~{WP})") (class "Default")
      (node (ref "R17") (pin "1") (pinfunction "1_1") (pintype "passive"))
      (node (ref "U9") (pin "3") (pinfunction "~{WP}_3") (pintype "passive"))
    )
    (net (code "47") (name "VCC_1V2") (class "Default")
      (node (ref "C1") (pin "1") (pinfunction "1_1") (pintype "passive"))
      (node (ref "C28") (pin "1") (pinfunction "1_1") (pintype "passive"))
      (node (ref "C31") (pin "1") (pinfunction "1_1") (pintype "passive"))
      (node (ref "C34") (pin "1") (pinfunction "1_1") (pintype "passive"))
      (node (ref "C36") (pin "1") (pinfunction "1_1") (pintype "passive"))
      (node (ref "C41") (pin "1") (pinfunction "1_1") (pintype "passive"))
      (node (ref "C42") (pin "1") (pinfunction "1_1") (pintype "passive"))
      (node (ref "TP1") (pin "1") (pinfunction "1_1") (pintype "passive"))
      (node (ref "U1") (pin "2") (pinfunction "Vout_2") (pintype "passive"))
      (node (ref "U5") (pin "111") (pinfunction "VCC_111") (pintype "power_in"))
      (node (ref "U5") (pin "126") (pinfunction "VCCPLL1_126") (pintype "power_in"))
      (node (ref "U5") (pin "27") (pinfunction "VCC_27") (pintype "power_in"))
      (node (ref "U5") (pin "40") (pinfunction "VCC_40") (pintype "power_in"))
      (node (ref "U5") (pin "54") (pinfunction "VCCPLL0_54") (pintype "power_in"))
      (node (ref "U5") (pin "92") (pinfunction "VCC_92") (pintype "power_in"))
    )
    (net (code "48") (name "VCC_3V3") (class "Default")
      (node (ref "C11") (pin "1") (pinfunction "1_1") (pintype "passive"))
      (node (ref "C21") (pin "2") (pinfunction "2_2") (pintype "passive"))
      (node (ref "C32") (pin "1") (pinfunction "1_1") (pintype "passive"))
      (node (ref "C37") (pin "1") (pinfunction "1_1") (pintype "passive"))
      (node (ref "C38") (pin "1") (pinfunction "1_1") (pintype "passive"))
      (node (ref "C39") (pin "1") (pinfunction "1_1") (pintype "passive"))
      (node (ref "C40") (pin "1") (pinfunction "1_1") (pintype "passive"))
      (node (ref "R14") (pin "2") (pinfunction "2_2") (pintype "passive"))
      (node (ref "R15") (pin "2") (pinfunction "2_2") (pintype "passive"))
      (node (ref "R17") (pin "2") (pinfunction "2_2") (pintype "passive"))
      (node (ref "R18") (pin "2") (pinfunction "2_2") (pintype "passive"))
      (node (ref "R26") (pin "1") (pinfunction "1_1") (pintype "passive"))
      (node (ref "R27") (pin "1") (pinfunction "1_1") (pintype "passive"))
      (node (ref "R3") (pin "1") (pinfunction "1_1") (pintype "passive"))
      (node (ref "TP3") (pin "1") (pinfunction "1_1") (pintype "passive"))
      (node (ref "U3") (pin "2") (pinfunction "Vout_2") (pintype "passive"))
      (node (ref "U5") (pin "30") (pinfunction "VCCIO_3_30") (pintype "power_in"))
      (node (ref "U5") (pin "46") (pinfunction "VCCIO_2_46") (pintype "power_in"))
      (node (ref "U5") (pin "57") (pinfunction "VCCIO_2_57") (pintype "power_in"))
      (node (ref "U5") (pin "6") (pinfunction "VCCIO_3_6") (pintype "power_in"))
      (node (ref "U5") (pin "72") (pinfunction "VCC_SPI_72") (pintype "power_in"))
      (node (ref "U9") (pin "8") (pinfunction "VCC_8") (pintype "passive"))
    )
    (net (code "49") (name "VCC_PWR") (class "Default")
      (node (ref "P1") (pin "1") (pinfunction "1_1") (pintype "passive"))
      (node (ref "R32") (pin "1") (pinfunction "1_1") (pintype "passive"))
      (node (ref "R33") (pin "1") (pinfunction "1_1") (pintype "passive"))
      (node (ref "R34") (pin "1") (pinfunction "1_1") (pintype "passive"))
      (node (ref "R35") (pin "2") (pinfunction "2_2") (pintype "passive"))
    )
    (net (code "50") (name "unconnected-(U5E-NC-Pad35)") (class "Default")
      (node (ref "U5") (pin "35") (pinfunction "NC_35") (pintype "passive+no_connect"))
    )
    (net (code "51") (name "unconnected-(U5E-NC-Pad36)") (class "Default")
      (node (ref "U5") (pin "36") (pinfunction "NC_36") (pintype "passive+no_connect"))
    )
    (net (code "52") (name "unconnected-(U5E-NC-Pad50)") (class "Default")
      (node (ref "U5") (pin "50") (pinfunction "NC_50") (pintype "passive+no_connect"))
    )
    (net (code "53") (name "unconnected-(U5E-NC-Pad51)") (class "Default")
      (node (ref "U5") (pin "51") (pinfunction "NC_51") (pintype "passive+no_connect"))
    )
    (net (code "54") (name "unconnected-(U5E-NC-Pad58)") (class "Default")
      (node (ref "U5") (pin "58") (pinfunction "NC_58") (pintype "passive+no_connect"))
    )
    (net (code "55") (name "unconnected-(U5E-NC-Pad77)") (class "Default")
      (node (ref "U5") (pin "77") (pinfunction "NC_77") (pintype "passive+no_connect"))
    )
    (net (code "56") (name "unconnected-(U5E-NC-Pad133)") (class "Default")
      (node (ref "U5") (pin "133") (pinfunction "NC_133") (pintype "passive+no_connect"))
    )
    (net (code "57") (name "unconnected-(U5E-VPP_FAST-Pad109)") (class "Default")
      (node (ref "U5") (pin "109") (pinfunction "VPP_FAST_109") (pintype "power_in+no_connect"))
    )
  )
)
